# 1_Power_Supply.net
KiCad netlist of a schematic drawn in Altium Designer
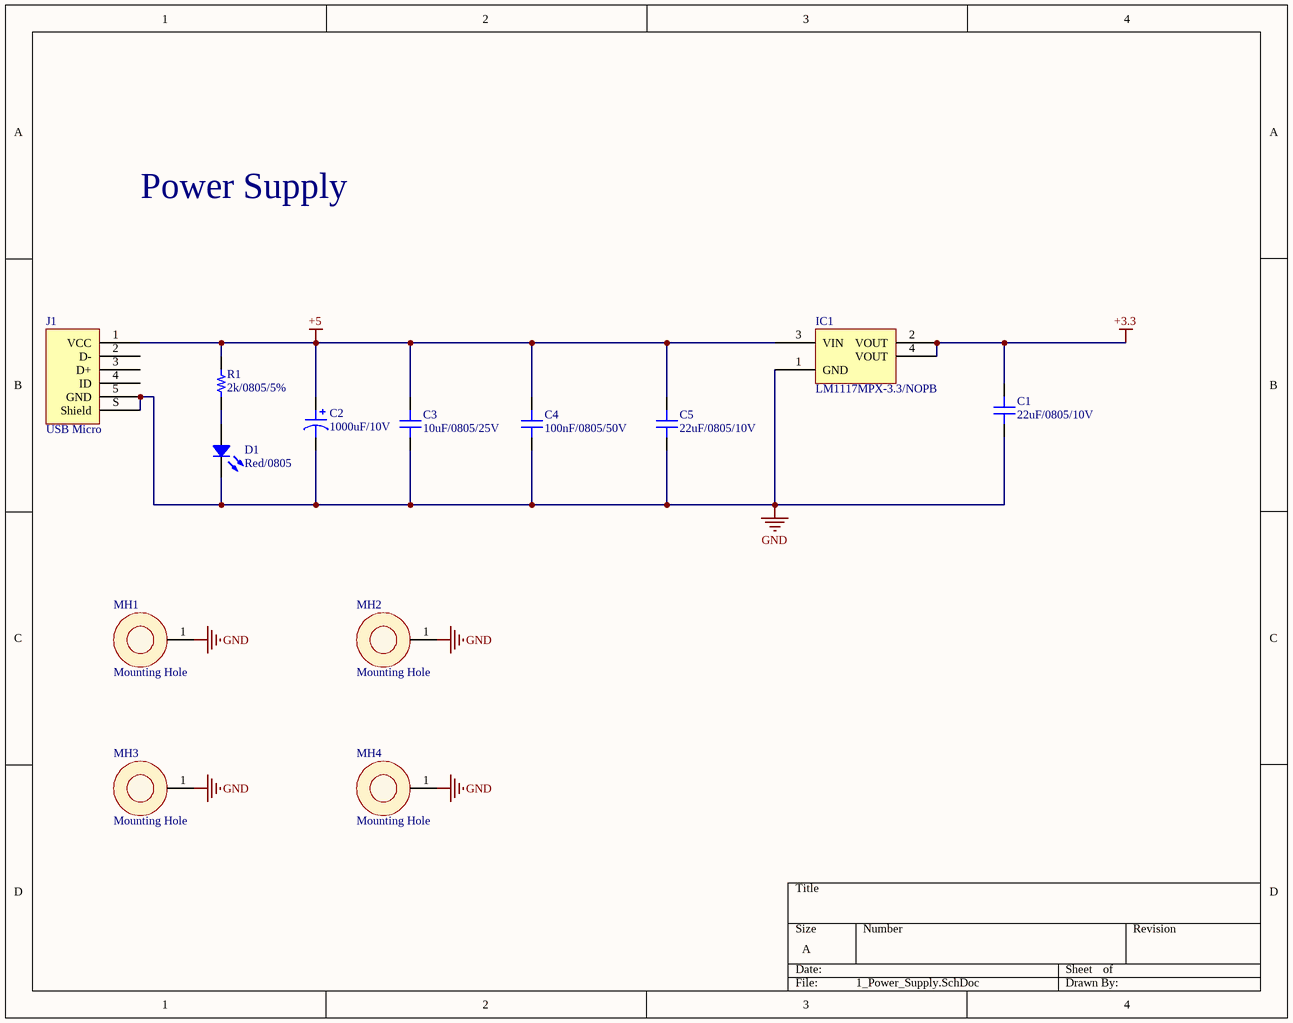
[diagram p0: 1_Power_Supply.SchDoc]

(export (version "E")
  (design (tool "Eeschema 10.0.6"))
  (components
    (comp (ref "C1")
      (value "22uF/0805/10V")
      (footprint "CAP 0805_2012")
      (description "Multilayer Ceramic Capacitor, 22 uF, 10 V, ± 20%, X5R, 0805 [2012 Metric]")
      (fields
        (field (name "MANUFACTURER") "Samsung")
        (field (name "MANUFACTURER PART NUMBER") "CL21A226MPQNNNE")
      )
      (libsource (lib "NLOC_Altium_Library") (part "Capacitor - MLCC"))
    )
    (comp (ref "C2")
      (value "1000uF/10V")
      (footprint "CAP ALSMD 4.3MM H5.4MM")
      (description "Aluminum Electrolytic Capacitor, 1000 uF, 10 V, ± 20%, 1000 hours @ 105°C, Radial Can - SMD")
      (fields
        (field (name "MANUFACTURER") "Panasonic")
        (field (name "MANUFACTURER PART NUMBER") "EEE-HA1A102P")
      )
      (libsource (lib "NLOC_Altium_Library") (part "Capacitor - Aluminum"))
    )
    (comp (ref "C3")
      (value "10uF/0805/25V")
      (footprint "CAP FILM 0805")
      (description "Multilayer Ceramic Capacitor, 10 uF, 25 V, ï¿½ 10%, X5R, 0805 [2012 Metric]")
      (fields
        (field (name "MANUFACTURER") "Samsung")
        (field (name "MANUFACTURER PART NUMBER") "CL21A106KAYNNNE")
      )
      (libsource (lib "NLOC_Altium_Library") (part "Capacitor - MLCC"))
    )
    (comp (ref "C4")
      (value "100nF/0805/50V")
      (footprint "CAP FILM 0805")
      (description "Multilayer Ceramic Capacitor, 0.1 uF, 50 V, ï¿½ 10%, X7R, 0805 [2012 Metric]")
      (fields
        (field (name "MANUFACTURER") "Samsung")
        (field (name "MANUFACTURER PART NUMBER") "CL21B104KBCNNNC")
      )
      (libsource (lib "NLOC_Altium_Library") (part "Capacitor - MLCC"))
    )
    (comp (ref "C5")
      (value "22uF/0805/10V")
      (footprint "CAP 0805_2012")
      (description "Multilayer Ceramic Capacitor, 22 uF, 10 V, ± 20%, X5R, 0805 [2012 Metric]")
      (fields
        (field (name "MANUFACTURER") "Samsung")
        (field (name "MANUFACTURER PART NUMBER") "CL21A226MPQNNNE")
      )
      (libsource (lib "NLOC_Altium_Library") (part "Capacitor - MLCC"))
    )
    (comp (ref "D1")
      (value "Red/0805")
      (footprint "LED 0805_2012 RED")
      (description "LED Uni-Color Red 2-Pin Chip 0805(2012Metric) T/R")
      (fields (field (name "MANUFACTURER") "Rohm") (field (name "MANUFACTURER PART NUMBER") "SML-H12U8TT86"))
      (libsource (lib "NLOC_Altium_Library") (part "LED"))
    )
    (comp (ref "IC1")
      (value "LM1117MPX-3.3/NOPB")
      (footprint "TI SOT-223 DCY")
      (description "800-mA 15-V linear voltage regulator ; 4-SOT-223 0 to 125")
      (fields (field (name "MANUFACTURER") "Texas Instruments"))
      (libsource (lib "NLOC_Altium_Library") (part "LM1117IMP/NOPB"))
    )
    (comp (ref "J1")
      (value "USB Micro")
      (footprint "FCI USB 10118193-0001LF")
      (libsource (lib "NLOC_Altium_Library") (part "USB 2.0 Type B Micro"))
    )
    (comp (ref "MH1")
      (value "Mounting Hole")
      (footprint "M3_Hole")
      (description "Mounting hole")
      (libsource (lib "NLOC_Altium_Library") (part "Mounting Hole"))
    )
    (comp (ref "MH2")
      (value "Mounting Hole")
      (footprint "M3_Hole")
      (description "Mounting hole")
      (libsource (lib "NLOC_Altium_Library") (part "Mounting Hole"))
    )
    (comp (ref "MH3")
      (value "Mounting Hole")
      (footprint "M3_Hole")
      (description "Mounting hole")
      (libsource (lib "NLOC_Altium_Library") (part "Mounting Hole"))
    )
    (comp (ref "MH4")
      (value "Mounting Hole")
      (footprint "M3_Hole")
      (description "Mounting hole")
      (libsource (lib "NLOC_Altium_Library") (part "Mounting Hole"))
    )
    (comp (ref "R1")
      (value "2k/0805/5%")
      (footprint "RES 0805_2012")
      (description "Res Thin Film 0805 2K Ohm 0.1% 0.125W(1/8W) ±25ppm/C Pad SMD T/R")
      (fields
        (field (name "MANUFACTURER") "Yageo")
        (field (name "MANUFACTURER PART NUMBER") "RT0805BRD072KL")
      )
      (libsource (lib "NLOC_Altium_Library") (part "Resistor"))
    )
  )
  (nets
    (net (code "1") (name "+3.3") (class "Default")
      (node (ref "C1") (pin "1") (pinfunction "1_1") (pintype "passive"))
      (node (ref "IC1") (pin "2") (pinfunction "VOUT_2") (pintype "passive"))
      (node (ref "IC1") (pin "4") (pinfunction "VOUT_4") (pintype "passive"))
    )
    (net (code "2") (name "+5") (class "Default")
      (node (ref "C2") (pin "1") (pinfunction "1_1") (pintype "passive"))
      (node (ref "C3") (pin "2") (pinfunction "2_2") (pintype "passive"))
      (node (ref "C4") (pin "2") (pinfunction "2_2") (pintype "passive"))
      (node (ref "C5") (pin "1") (pinfunction "1_1") (pintype "passive"))
      (node (ref "IC1") (pin "3") (pinfunction "VIN_3") (pintype "passive"))
      (node (ref "J1") (pin "1") (pinfunction "VCC_1") (pintype "passive"))
      (node (ref "R1") (pin "2") (pinfunction "2_2") (pintype "passive"))
    )
    (net (code "3") (name "GND") (class "Default")
      (node (ref "C1") (pin "2") (pinfunction "2_2") (pintype "passive"))
      (node (ref "C2") (pin "2") (pinfunction "2_2") (pintype "passive"))
      (node (ref "C3") (pin "1") (pinfunction "1_1") (pintype "passive"))
      (node (ref "C4") (pin "1") (pinfunction "1_1") (pintype "passive"))
      (node (ref "C5") (pin "2") (pinfunction "2_2") (pintype "passive"))
      (node (ref "D1") (pin "2") (pinfunction "2_2") (pintype "passive"))
      (node (ref "IC1") (pin "1") (pinfunction "GND_1") (pintype "passive"))
      (node (ref "J1") (pin "5") (pinfunction "GND_5") (pintype "passive"))
      (node (ref "J1") (pin "S") (pinfunction "Shield_S") (pintype "passive"))
      (node (ref "MH1") (pin "1") (pinfunction "FG_1") (pintype "passive"))
      (node (ref "MH2") (pin "1") (pinfunction "FG_1") (pintype "passive"))
      (node (ref "MH3") (pin "1") (pinfunction "FG_1") (pintype "passive"))
      (node (ref "MH4") (pin "1") (pinfunction "FG_1") (pintype "passive"))
    )
    (net (code "4") (name "Net-(D1-Pad1)") (class "Default")
      (node (ref "D1") (pin "1") (pinfunction "1_1") (pintype "passive"))
      (node (ref "R1") (pin "1") (pinfunction "1_1") (pintype "passive"))
    )
    (net (code "5") (name "unconnected-(J1-D+-Pad3)") (class "Default")
      (node (ref "J1") (pin "3") (pinfunction "D+_3") (pintype "passive"))
    )
    (net (code "6") (name "unconnected-(J1-D--Pad2)") (class "Default")
      (node (ref "J1") (pin "2") (pinfunction "D-_2") (pintype "passive"))
    )
    (net (code "7") (name "unconnected-(J1-ID-Pad4)") (class "Default")
      (node (ref "J1") (pin "4") (pinfunction "ID_4") (pintype "passive"))
    )
  )
)
